# MethaneFlux_-_Copy.net
KiCad netlist of a schematic drawn in EAGLE
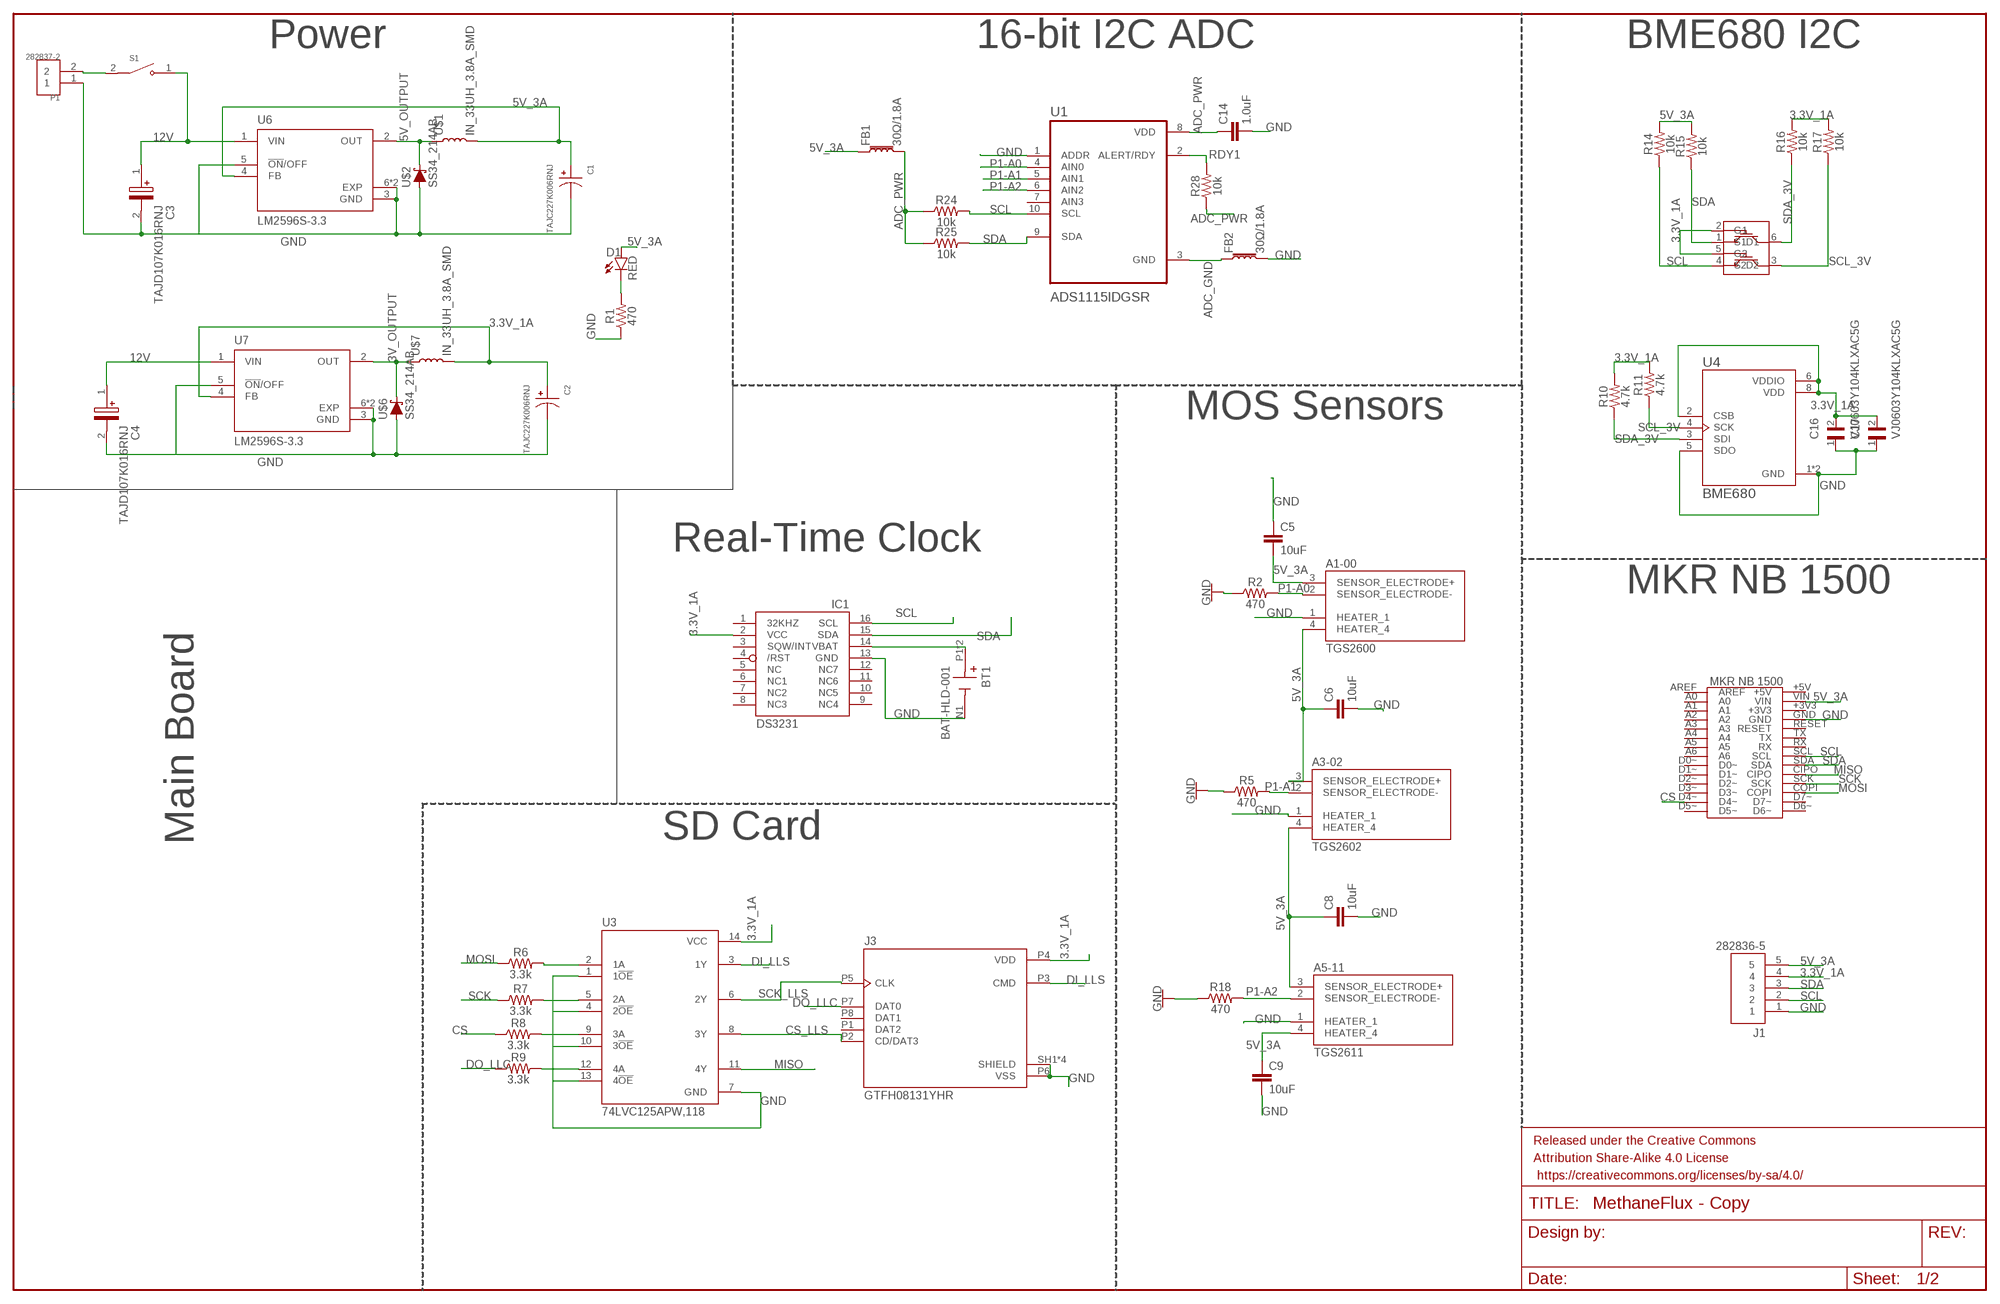
[diagram p0: schematic, sheet 1]
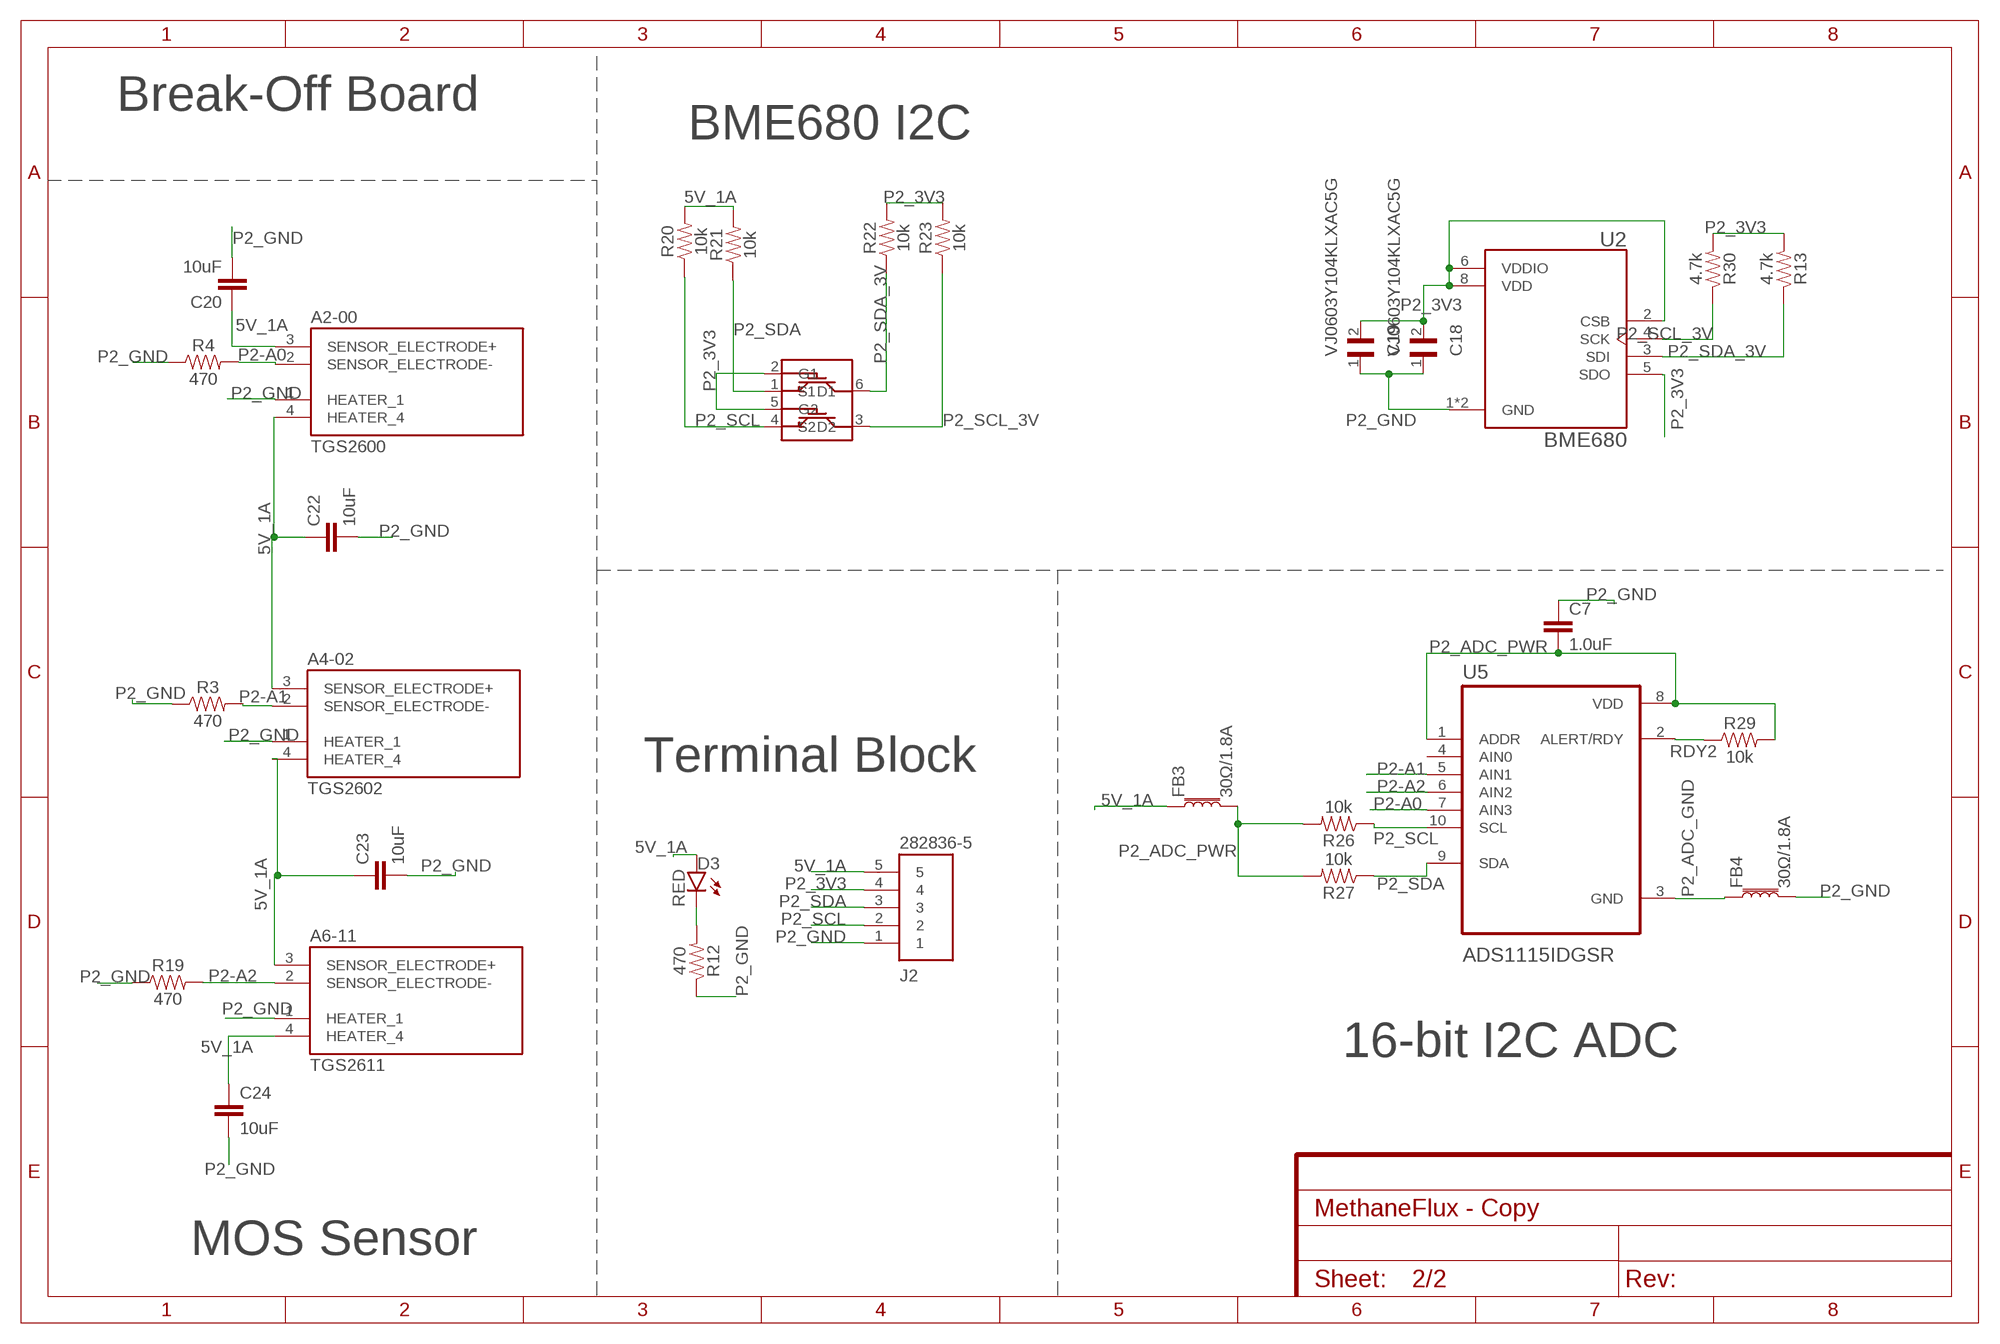
[diagram p1: schematic, sheet 2]

(export (version "E")
  (design (tool "Eeschema 10.0.6"))
  (components
    (comp (ref "A2-00")
      (value "TGS2600")
      (footprint "eagle-import:TO255P920H830-4")
      (fields (field (name "MF") "Figaro"))
      (libsource (lib "eagle-import") (part "TGS2600"))
    )
    (comp (ref "A4-02")
      (value "TGS2602")
      (footprint "eagle-import:TGS2602")
      (libsource (lib "eagle-import") (part "TGS2602"))
    )
    (comp (ref "A6-11")
      (value "TGS2611")
      (footprint "eagle-import:TGS2611")
      (libsource (lib "eagle-import") (part "TGS2611"))
    )
    (comp (ref "C7")
      (value "1.0uF")
      (footprint "eagle-import:0603")
      (libsource (lib "eagle-import") (part "1.0UF-0603-16V-10%"))
    )
    (comp (ref "C18")
      (value "VJ0603Y104KLXAC5G")
      (footprint "eagle-import:CAPC1608X92N")
      (fields (field (name "MF") "Vishay"))
      (libsource (lib "eagle-import") (part "VJ0603Y104KLXAC5G"))
    )
    (comp (ref "C19")
      (value "VJ0603Y104KLXAC5G")
      (footprint "eagle-import:CAPC1608X92N")
      (fields (field (name "MF") "Vishay"))
      (libsource (lib "eagle-import") (part "VJ0603Y104KLXAC5G"))
    )
    (comp (ref "C20")
      (value "10uF")
      (footprint "eagle-import:0603")
      (libsource (lib "eagle-import") (part "10UF-0603-6.3V-20%"))
    )
    (comp (ref "C22")
      (value "10uF")
      (footprint "eagle-import:0603")
      (libsource (lib "eagle-import") (part "10UF-0603-6.3V-20%"))
    )
    (comp (ref "C23")
      (value "10uF")
      (footprint "eagle-import:0603")
      (libsource (lib "eagle-import") (part "10UF-0603-6.3V-20%"))
    )
    (comp (ref "C24")
      (value "10uF")
      (footprint "eagle-import:0603")
      (libsource (lib "eagle-import") (part "10UF-0603-6.3V-20%"))
    )
    (comp (ref "D3")
      (value "RED")
      (footprint "eagle-import:LED-0603")
      (libsource (lib "eagle-import") (part "LED-RED0603"))
    )
    (comp (ref "FB3")
      (value "30Ω/1.8A")
      (footprint "eagle-import:0603")
      (libsource (lib "eagle-import") (part "FERRITE_BEAD-0603"))
    )
    (comp (ref "FB4")
      (value "30Ω/1.8A")
      (footprint "eagle-import:0603")
      (libsource (lib "eagle-import") (part "FERRITE_BEAD-0603"))
    )
    (comp (ref "J2")
      (value "282836-5")
      (footprint "eagle-import:TE_282836-5")
      (fields (field (name "MF") "TE Connectivity"))
      (libsource (lib "eagle-import") (part "282836-5"))
    )
    (comp (ref "R3")
      (value "470")
      (footprint "eagle-import:0603")
      (libsource (lib "eagle-import") (part "470OHM-0603-1/10W-1%"))
    )
    (comp (ref "R4")
      (value "470")
      (footprint "eagle-import:0603")
      (libsource (lib "eagle-import") (part "470OHM-0603-1/10W-1%"))
    )
    (comp (ref "R12")
      (value "470")
      (footprint "eagle-import:0603")
      (libsource (lib "eagle-import") (part "470OHM-0603-1/10W-1%"))
    )
    (comp (ref "R13")
      (value "4.7k")
      (footprint "eagle-import:0603")
      (libsource (lib "eagle-import") (part "4.7KOHM-0603-1/10W-1%"))
    )
    (comp (ref "R19")
      (value "470")
      (footprint "eagle-import:0603")
      (libsource (lib "eagle-import") (part "470OHM-0603-1/10W-1%"))
    )
    (comp (ref "R20")
      (value "10k")
      (footprint "eagle-import:0603")
      (libsource (lib "eagle-import") (part "10KOHM-0603-1/10W-1%"))
    )
    (comp (ref "R21")
      (value "10k")
      (footprint "eagle-import:0603")
      (libsource (lib "eagle-import") (part "10KOHM-0603-1/10W-1%"))
    )
    (comp (ref "R22")
      (value "10k")
      (footprint "eagle-import:0603")
      (libsource (lib "eagle-import") (part "10KOHM-0603-1/10W-1%"))
    )
    (comp (ref "R23")
      (value "10k")
      (footprint "eagle-import:0603")
      (libsource (lib "eagle-import") (part "10KOHM-0603-1/10W-1%"))
    )
    (comp (ref "R26")
      (value "10k")
      (footprint "eagle-import:0603")
      (libsource (lib "eagle-import") (part "10KOHM-0603-1/10W-1%"))
    )
    (comp (ref "R27")
      (value "10k")
      (footprint "eagle-import:0603")
      (libsource (lib "eagle-import") (part "10KOHM-0603-1/10W-1%"))
    )
    (comp (ref "R29")
      (value "10k")
      (footprint "eagle-import:0603")
      (libsource (lib "eagle-import") (part "10KOHM-0603-1/10W-1%"))
    )
    (comp (ref "R30")
      (value "4.7k")
      (footprint "eagle-import:0603")
      (libsource (lib "eagle-import") (part "4.7KOHM-0603-1/10W-1%"))
    )
    (comp (ref "U$4")
      (value "2N7002DW")
      (footprint "eagle-import:SOT363")
      (fields (field (name "MF") "onsemi"))
      (libsource (lib "eagle-import") (part "2N7002DW"))
    )
    (comp (ref "U2")
      (value "BME680")
      (footprint "eagle-import:PSON80P300X300X100-8N")
      (fields (field (name "MF") "Bosch Sensortec"))
      (libsource (lib "eagle-import") (part "BME680"))
    )
    (comp (ref "U5")
      (value "ADS1115IDGSR")
      (footprint "eagle-import:SOP50P490X110-10N")
      (fields (field (name "MF") "Texas Instruments"))
      (libsource (lib "eagle-import") (part "ADS1115IDGSR"))
    )
    (comp (ref "A1-00")
      (value "TGS2600")
      (footprint "eagle-import:TO255P920H830-4")
      (fields (field (name "MF") "Figaro"))
      (libsource (lib "eagle-import") (part "TGS2600"))
    )
    (comp (ref "A3-02")
      (value "TGS2602")
      (footprint "eagle-import:TGS2602")
      (libsource (lib "eagle-import") (part "TGS2602"))
    )
    (comp (ref "A5-11")
      (value "TGS2611")
      (footprint "eagle-import:TGS2611")
      (libsource (lib "eagle-import") (part "TGS2611"))
    )
    (comp (ref "BT1")
      (value "BAT-HLD-001")
      (footprint "eagle-import:BAT_BAT-HLD-001")
      (fields (field (name "MF") "Linx Technologies"))
      (libsource (lib "eagle-import") (part "BAT-HLD-001"))
    )
    (comp (ref "C1")
      (value "TAJC227K006RNJ")
      (footprint "eagle-import:CAPPM6032X280N")
      (fields (field (name "DIGIKEY_PART_NUMBER") "478-1713-2-ND") (field (name "MF") "KYOCERA AVX"))
      (libsource (lib "eagle-import") (part "TAJC227K006RNJ"))
    )
    (comp (ref "C2")
      (value "TAJC227K006RNJ")
      (footprint "eagle-import:CAPPM6032X280N")
      (fields (field (name "DIGIKEY_PART_NUMBER") "478-1713-2-ND") (field (name "MF") "KYOCERA AVX"))
      (libsource (lib "eagle-import") (part "TAJC227K006RNJ"))
    )
    (comp (ref "C3")
      (value "TAJD107K016RNJ")
      (footprint "eagle-import:CAPPM7344X310N")
      (fields (field (name "MF") "AVX"))
      (libsource (lib "eagle-import") (part "TAJD107K016RNJ"))
    )
    (comp (ref "C4")
      (value "TAJD107K016RNJ")
      (footprint "eagle-import:CAPPM7344X310N")
      (fields (field (name "MF") "AVX"))
      (libsource (lib "eagle-import") (part "TAJD107K016RNJ"))
    )
    (comp (ref "C5")
      (value "10uF")
      (footprint "eagle-import:0603")
      (libsource (lib "eagle-import") (part "10UF-0603-6.3V-20%"))
    )
    (comp (ref "C6")
      (value "10uF")
      (footprint "eagle-import:0603")
      (libsource (lib "eagle-import") (part "10UF-0603-6.3V-20%"))
    )
    (comp (ref "C8")
      (value "10uF")
      (footprint "eagle-import:0603")
      (libsource (lib "eagle-import") (part "10UF-0603-6.3V-20%"))
    )
    (comp (ref "C9")
      (value "10uF")
      (footprint "eagle-import:0603")
      (libsource (lib "eagle-import") (part "10UF-0603-6.3V-20%"))
    )
    (comp (ref "C14")
      (value "1.0uF")
      (footprint "eagle-import:0603")
      (libsource (lib "eagle-import") (part "1.0UF-0603-16V-10%"))
    )
    (comp (ref "C16")
      (value "VJ0603Y104KLXAC5G")
      (footprint "eagle-import:CAPC1608X92N")
      (fields (field (name "MF") "Vishay"))
      (libsource (lib "eagle-import") (part "VJ0603Y104KLXAC5G"))
    )
    (comp (ref "C17")
      (value "VJ0603Y104KLXAC5G")
      (footprint "eagle-import:CAPC1608X92N")
      (fields (field (name "MF") "Vishay"))
      (libsource (lib "eagle-import") (part "VJ0603Y104KLXAC5G"))
    )
    (comp (ref "D1")
      (value "RED")
      (footprint "eagle-import:LED-0603")
      (libsource (lib "eagle-import") (part "LED-RED0603"))
    )
    (comp (ref "FB1")
      (value "30Ω/1.8A")
      (footprint "eagle-import:0603")
      (libsource (lib "eagle-import") (part "FERRITE_BEAD-0603"))
    )
    (comp (ref "FB2")
      (value "30Ω/1.8A")
      (footprint "eagle-import:0603")
      (libsource (lib "eagle-import") (part "FERRITE_BEAD-0603"))
    )
    (comp (ref "FRAME1")
      (value "FRAME-LEDGER")
      (footprint "eagle-import:CREATIVE_COMMONS")
      (libsource (lib "eagle-import") (part "FRAME-LEDGER"))
    )
    (comp (ref "IC1")
      (value "DS3231/SO")
      (footprint "eagle-import:SO16W")
      (fields (field (name "MF") "Analog Devices") (field (name "MP") "DS3231"))
      (libsource (lib "eagle-import") (part "DS3231/SO"))
    )
    (comp (ref "J1")
      (value "282836-5")
      (footprint "eagle-import:TE_282836-5")
      (fields (field (name "MF") "TE Connectivity"))
      (libsource (lib "eagle-import") (part "282836-5"))
    )
    (comp (ref "J3")
      (value "GTFH08131YHR")
      (footprint "eagle-import:AMPHENOL_GTFH08131YHR")
      (fields (field (name "MF") "Amphenol ICC"))
      (libsource (lib "eagle-import") (part "GTFH08131YHR"))
    )
    (comp (ref "P1")
      (value "282837-2")
      (footprint "eagle-import:TE_282837-2")
      (fields (field (name "MF") "TE Connectivity"))
      (libsource (lib "eagle-import") (part "282837-2"))
    )
    (comp (ref "R1")
      (value "470")
      (footprint "eagle-import:0603")
      (libsource (lib "eagle-import") (part "470OHM-0603-1/10W-1%"))
    )
    (comp (ref "R2")
      (value "470")
      (footprint "eagle-import:0603")
      (libsource (lib "eagle-import") (part "470OHM-0603-1/10W-1%"))
    )
    (comp (ref "R5")
      (value "470")
      (footprint "eagle-import:0603")
      (libsource (lib "eagle-import") (part "470OHM-0603-1/10W-1%"))
    )
    (comp (ref "R6")
      (value "3.3k")
      (footprint "eagle-import:0603")
      (libsource (lib "eagle-import") (part "3.3KOHM-0603-1/10W-1%"))
    )
    (comp (ref "R7")
      (value "3.3k")
      (footprint "eagle-import:0603")
      (libsource (lib "eagle-import") (part "3.3KOHM-0603-1/10W-1%"))
    )
    (comp (ref "R8")
      (value "3.3k")
      (footprint "eagle-import:0603")
      (libsource (lib "eagle-import") (part "3.3KOHM-0603-1/10W-1%"))
    )
    (comp (ref "R9")
      (value "3.3k")
      (footprint "eagle-import:0603")
      (libsource (lib "eagle-import") (part "3.3KOHM-0603-1/10W-1%"))
    )
    (comp (ref "R10")
      (value "4.7k")
      (footprint "eagle-import:0603")
      (libsource (lib "eagle-import") (part "4.7KOHM-0603-1/10W-1%"))
    )
    (comp (ref "R11")
      (value "4.7k")
      (footprint "eagle-import:0603")
      (libsource (lib "eagle-import") (part "4.7KOHM-0603-1/10W-1%"))
    )
    (comp (ref "R14")
      (value "10k")
      (footprint "eagle-import:0603")
      (libsource (lib "eagle-import") (part "10KOHM-0603-1/10W-1%"))
    )
    (comp (ref "R15")
      (value "10k")
      (footprint "eagle-import:0603")
      (libsource (lib "eagle-import") (part "10KOHM-0603-1/10W-1%"))
    )
    (comp (ref "R16")
      (value "10k")
      (footprint "eagle-import:0603")
      (libsource (lib "eagle-import") (part "10KOHM-0603-1/10W-1%"))
    )
    (comp (ref "R17")
      (value "10k")
      (footprint "eagle-import:0603")
      (libsource (lib "eagle-import") (part "10KOHM-0603-1/10W-1%"))
    )
    (comp (ref "R18")
      (value "470")
      (footprint "eagle-import:0603")
      (libsource (lib "eagle-import") (part "470OHM-0603-1/10W-1%"))
    )
    (comp (ref "R24")
      (value "10k")
      (footprint "eagle-import:0603")
      (libsource (lib "eagle-import") (part "10KOHM-0603-1/10W-1%"))
    )
    (comp (ref "R25")
      (value "10k")
      (footprint "eagle-import:0603")
      (libsource (lib "eagle-import") (part "10KOHM-0603-1/10W-1%"))
    )
    (comp (ref "R28")
      (value "10k")
      (footprint "eagle-import:0603")
      (libsource (lib "eagle-import") (part "10KOHM-0603-1/10W-1%"))
    )
    (comp (ref "S1")
      (value "RB141C1100")
      (footprint "eagle-import:SW_RB141C1100")
      (fields (field (name "MF") "E-Switch"))
      (libsource (lib "eagle-import") (part "RB141C1100"))
    )
    (comp (ref "U$1")
      (value "IN_33UH_3.8A_SMD")
      (footprint "eagle-import:INDUCTOR_4X4MM")
      (libsource (lib "eagle-import") (part "IN_33UH_3.8A_SMD"))
    )
    (comp (ref "U$2")
      (value "SS34_214AB")
      (footprint "eagle-import:SOD-323")
      (libsource (lib "eagle-import") (part "SS34_214AB"))
    )
    (comp (ref "U$3")
      (value "2N7002DW")
      (footprint "eagle-import:SOT363")
      (fields (field (name "MF") "onsemi"))
      (libsource (lib "eagle-import") (part "2N7002DW"))
    )
    (comp (ref "U$5")
      (value "MKRNB1500")
      (footprint "eagle-import:MRKNB1500")
      (libsource (lib "eagle-import") (part "MKRNB1500"))
    )
    (comp (ref "U$6")
      (value "SS34_214AB")
      (footprint "eagle-import:SOD-323")
      (libsource (lib "eagle-import") (part "SS34_214AB"))
    )
    (comp (ref "U$7")
      (value "IN_33UH_3.8A_SMD")
      (footprint "eagle-import:INDUCTOR_4X4MM")
      (libsource (lib "eagle-import") (part "IN_33UH_3.8A_SMD"))
    )
    (comp (ref "U1")
      (value "ADS1115IDGSR")
      (footprint "eagle-import:SOP50P490X110-10N")
      (fields (field (name "MF") "Texas Instruments"))
      (libsource (lib "eagle-import") (part "ADS1115IDGSR"))
    )
    (comp (ref "U3")
      (value "74LVC125APW,118")
      (footprint "eagle-import:IC_74LVC125APW,118")
      (fields (field (name "MF") "Nexperia USA Inc."))
      (libsource (lib "eagle-import") (part "74LVC125APW,118"))
    )
    (comp (ref "U4")
      (value "BME680")
      (footprint "eagle-import:PSON80P300X300X100-8N")
      (fields (field (name "MF") "Bosch Sensortec"))
      (libsource (lib "eagle-import") (part "BME680"))
    )
    (comp (ref "U6")
      (value "LM2596S-3.3")
      (footprint "eagle-import:VREG_LM2596S-3.3")
      (fields (field (name "MF") "Texas Instruments"))
      (libsource (lib "eagle-import") (part "LM2596S-3.3"))
    )
    (comp (ref "U7")
      (value "LM2596S-3.3")
      (footprint "eagle-import:VREG_LM2596S-3.3")
      (fields (field (name "MF") "Texas Instruments"))
      (libsource (lib "eagle-import") (part "LM2596S-3.3"))
    )
  )
  (nets
    (net (code "1") (name "3.3V_1A") (class "Default")
      (node (ref "C16") (pin "2") (pinfunction "2_2") (pintype "passive"))
      (node (ref "C17") (pin "2") (pinfunction "2_2") (pintype "passive"))
      (node (ref "C2") (pin "1") (pinfunction "1_1") (pintype "passive"))
      (node (ref "IC1") (pin "2") (pinfunction "VCC_2") (pintype "power_in"))
      (node (ref "J1") (pin "4") (pinfunction "4_4") (pintype "passive"))
      (node (ref "J3") (pin "P4") (pinfunction "VDD_P4") (pintype "power_in"))
      (node (ref "R10") (pin "2") (pinfunction "2_2") (pintype "passive"))
      (node (ref "R11") (pin "2") (pinfunction "2_2") (pintype "passive"))
      (node (ref "R16") (pin "2") (pinfunction "2_2") (pintype "passive"))
      (node (ref "R17") (pin "2") (pinfunction "2_2") (pintype "passive"))
      (node (ref "U$3") (pin "2") (pinfunction "G1_2") (pintype "bidirectional"))
      (node (ref "U$3") (pin "5") (pinfunction "G2_5") (pintype "bidirectional"))
      (node (ref "U$7") (pin "P$2") (pinfunction "2_P$2") (pintype "passive"))
      (node (ref "U3") (pin "14") (pinfunction "VCC_14") (pintype "power_in"))
      (node (ref "U4") (pin "2") (pinfunction "CSB_2") (pintype "input"))
      (node (ref "U4") (pin "6") (pinfunction "VDDIO_6") (pintype "power_in"))
      (node (ref "U4") (pin "8") (pinfunction "VDD_8") (pintype "power_in"))
      (node (ref "U7") (pin "4") (pinfunction "FB_4") (pintype "input"))
    )
    (net (code "2") (name "3V_OUTPUT") (class "Default")
      (node (ref "U$6") (pin "ANODE") (pinfunction "C_ANODE") (pintype "passive"))
      (node (ref "U$7") (pin "P$1") (pinfunction "1_P$1") (pintype "passive"))
      (node (ref "U7") (pin "2") (pinfunction "OUT_2") (pintype "output"))
    )
    (net (code "3") (name "5V_1A") (class "Default")
      (node (ref "A2-00") (pin "3") (pinfunction "SENSOR_ELECTRODE+_3") (pintype "passive"))
      (node (ref "A2-00") (pin "4") (pinfunction "HEATER_4_4") (pintype "passive"))
      (node (ref "A4-02") (pin "3") (pinfunction "SENSOR_ELECTRODE+_3") (pintype "passive"))
      (node (ref "A4-02") (pin "4") (pinfunction "HEATER_4_4") (pintype "passive"))
      (node (ref "A6-11") (pin "3") (pinfunction "SENSOR_ELECTRODE+_3") (pintype "passive"))
      (node (ref "A6-11") (pin "4") (pinfunction "HEATER_4_4") (pintype "passive"))
      (node (ref "C20") (pin "1") (pinfunction "1_1") (pintype "passive"))
      (node (ref "C22") (pin "1") (pinfunction "1_1") (pintype "passive"))
      (node (ref "C23") (pin "1") (pinfunction "1_1") (pintype "passive"))
      (node (ref "C24") (pin "1") (pinfunction "1_1") (pintype "passive"))
      (node (ref "D3") (pin "A") (pinfunction "A_A") (pintype "passive"))
      (node (ref "FB3") (pin "1") (pinfunction "1_1") (pintype "passive"))
      (node (ref "J2") (pin "5") (pinfunction "5_5") (pintype "passive"))
      (node (ref "R20") (pin "2") (pinfunction "2_2") (pintype "passive"))
      (node (ref "R21") (pin "2") (pinfunction "2_2") (pintype "passive"))
    )
    (net (code "4") (name "5V_3A") (class "Default")
      (node (ref "A1-00") (pin "3") (pinfunction "SENSOR_ELECTRODE+_3") (pintype "passive"))
      (node (ref "A1-00") (pin "4") (pinfunction "HEATER_4_4") (pintype "passive"))
      (node (ref "A3-02") (pin "3") (pinfunction "SENSOR_ELECTRODE+_3") (pintype "passive"))
      (node (ref "A3-02") (pin "4") (pinfunction "HEATER_4_4") (pintype "passive"))
      (node (ref "A5-11") (pin "3") (pinfunction "SENSOR_ELECTRODE+_3") (pintype "passive"))
      (node (ref "A5-11") (pin "4") (pinfunction "HEATER_4_4") (pintype "passive"))
      (node (ref "C1") (pin "1") (pinfunction "1_1") (pintype "passive"))
      (node (ref "C5") (pin "2") (pinfunction "2_2") (pintype "passive"))
      (node (ref "C6") (pin "1") (pinfunction "1_1") (pintype "passive"))
      (node (ref "C8") (pin "1") (pinfunction "1_1") (pintype "passive"))
      (node (ref "C9") (pin "1") (pinfunction "1_1") (pintype "passive"))
      (node (ref "D1") (pin "A") (pinfunction "A_A") (pintype "passive"))
      (node (ref "FB1") (pin "1") (pinfunction "1_1") (pintype "passive"))
      (node (ref "J1") (pin "5") (pinfunction "5_5") (pintype "passive"))
      (node (ref "R14") (pin "2") (pinfunction "2_2") (pintype "passive"))
      (node (ref "R15") (pin "2") (pinfunction "2_2") (pintype "passive"))
      (node (ref "U$1") (pin "P$2") (pinfunction "2_P$2") (pintype "passive"))
      (node (ref "U$5") (pin "VIN") (pinfunction "VIN_VIN") (pintype "bidirectional"))
      (node (ref "U6") (pin "4") (pinfunction "FB_4") (pintype "input"))
    )
    (net (code "5") (name "5V_OUTPUT") (class "Default")
      (node (ref "U$1") (pin "P$1") (pinfunction "1_P$1") (pintype "passive"))
      (node (ref "U$2") (pin "ANODE") (pinfunction "C_ANODE") (pintype "passive"))
      (node (ref "U6") (pin "2") (pinfunction "OUT_2") (pintype "output"))
    )
    (net (code "6") (name "12V") (class "Default")
      (node (ref "C3") (pin "1") (pinfunction "+_1") (pintype "bidirectional"))
      (node (ref "C4") (pin "1") (pinfunction "+_1") (pintype "bidirectional"))
      (node (ref "S1") (pin "1") (pinfunction "1_1") (pintype "passive"))
      (node (ref "U6") (pin "1") (pinfunction "VIN_1") (pintype "input"))
      (node (ref "U7") (pin "1") (pinfunction "VIN_1") (pintype "input"))
    )
    (net (code "7") (name "ADC_GND") (class "Default")
      (node (ref "FB2") (pin "1") (pinfunction "1_1") (pintype "passive"))
      (node (ref "U1") (pin "3") (pinfunction "GND_3") (pintype "power_in"))
    )
    (net (code "8") (name "ADC_PWR") (class "Default")
      (node (ref "C14") (pin "1") (pinfunction "1_1") (pintype "passive"))
      (node (ref "FB1") (pin "2") (pinfunction "2_2") (pintype "passive"))
      (node (ref "R24") (pin "1") (pinfunction "1_1") (pintype "passive"))
      (node (ref "R25") (pin "1") (pinfunction "1_1") (pintype "passive"))
      (node (ref "R28") (pin "1") (pinfunction "1_1") (pintype "passive"))
      (node (ref "U1") (pin "8") (pinfunction "VDD_8") (pintype "power_in"))
    )
    (net (code "9") (name "CS") (class "Default")
      (node (ref "R8") (pin "1") (pinfunction "1_1") (pintype "passive"))
      (node (ref "U$5") (pin "D4~") (pinfunction "D4~{}_D4~") (pintype "bidirectional"))
    )
    (net (code "10") (name "CS_LLS") (class "Default")
      (node (ref "J3") (pin "P2") (pinfunction "CD/DAT3_P2") (pintype "bidirectional"))
      (node (ref "U3") (pin "8") (pinfunction "3Y_8") (pintype "output"))
    )
    (net (code "11") (name "DI_LLS") (class "Default")
      (node (ref "J3") (pin "P3") (pinfunction "CMD_P3") (pintype "bidirectional"))
      (node (ref "U3") (pin "3") (pinfunction "1Y_3") (pintype "output"))
    )
    (net (code "12") (name "DO_LLC") (class "Default")
      (node (ref "J3") (pin "P7") (pinfunction "DAT0_P7") (pintype "bidirectional"))
      (node (ref "R9") (pin "1") (pinfunction "1_1") (pintype "passive"))
    )
    (net (code "13") (name "GND") (class "Default")
      (node (ref "A1-00") (pin "1") (pinfunction "HEATER_1_1") (pintype "passive"))
      (node (ref "A3-02") (pin "1") (pinfunction "HEATER_1_1") (pintype "passive"))
      (node (ref "A5-11") (pin "1") (pinfunction "HEATER_1_1") (pintype "passive"))
      (node (ref "BT1") (pin "N1") (pinfunction "-_N1") (pintype "passive"))
      (node (ref "C1") (pin "2") (pinfunction "2_2") (pintype "passive"))
      (node (ref "C14") (pin "2") (pinfunction "2_2") (pintype "passive"))
      (node (ref "C16") (pin "1") (pinfunction "1_1") (pintype "passive"))
      (node (ref "C17") (pin "1") (pinfunction "1_1") (pintype "passive"))
      (node (ref "C2") (pin "2") (pinfunction "2_2") (pintype "passive"))
      (node (ref "C3") (pin "2") (pinfunction "-_2") (pintype "bidirectional"))
      (node (ref "C4") (pin "2") (pinfunction "-_2") (pintype "bidirectional"))
      (node (ref "C5") (pin "1") (pinfunction "1_1") (pintype "passive"))
      (node (ref "C6") (pin "2") (pinfunction "2_2") (pintype "passive"))
      (node (ref "C8") (pin "2") (pinfunction "2_2") (pintype "passive"))
      (node (ref "C9") (pin "2") (pinfunction "2_2") (pintype "passive"))
      (node (ref "FB2") (pin "2") (pinfunction "2_2") (pintype "passive"))
      (node (ref "IC1") (pin "13") (pinfunction "GND_13") (pintype "power_in"))
      (node (ref "J1") (pin "1") (pinfunction "1_1") (pintype "passive"))
      (node (ref "J3") (pin "P6") (pinfunction "VSS_P6") (pintype "power_in"))
      (node (ref "J3") (pin "SH1") (pinfunction "SHIELD_SH1") (pintype "power_in"))
      (node (ref "J3") (pin "SH2") (pinfunction "SHIELD_SH2") (pintype "power_in"))
      (node (ref "J3") (pin "SH3") (pinfunction "SHIELD_SH3") (pintype "power_in"))
      (node (ref "J3") (pin "SH4") (pinfunction "SHIELD_SH4") (pintype "power_in"))
      (node (ref "P1") (pin "1") (pinfunction "1_1") (pintype "passive"))
      (node (ref "R1") (pin "1") (pinfunction "1_1") (pintype "passive"))
      (node (ref "R18") (pin "1") (pinfunction "1_1") (pintype "passive"))
      (node (ref "R2") (pin "1") (pinfunction "1_1") (pintype "passive"))
      (node (ref "R5") (pin "1") (pinfunction "1_1") (pintype "passive"))
      (node (ref "U$2") (pin "CATHODE") (pinfunction "A_CATHODE") (pintype "passive"))
      (node (ref "U$5") (pin "GND") (pinfunction "GND_GND") (pintype "bidirectional"))
      (node (ref "U$6") (pin "CATHODE") (pinfunction "A_CATHODE") (pintype "passive"))
      (node (ref "U1") (pin "1") (pinfunction "ADDR_1") (pintype "input"))
      (node (ref "U3") (pin "1") (pinfunction "1~{OE}_1") (pintype "input"))
      (node (ref "U3") (pin "10") (pinfunction "3~{OE}_10") (pintype "input"))
      (node (ref "U3") (pin "13") (pinfunction "4~{OE}_13") (pintype "input"))
      (node (ref "U3") (pin "4") (pinfunction "2~{OE}_4") (pintype "input"))
      (node (ref "U3") (pin "7") (pinfunction "GND_7") (pintype "power_in"))
      (node (ref "U4") (pin "1") (pinfunction "GND_1") (pintype "power_in"))
      (node (ref "U4") (pin "5") (pinfunction "SDO_5") (pintype "bidirectional"))
      (node (ref "U4") (pin "7") (pinfunction "GND_7") (pintype "power_in"))
      (node (ref "U6") (pin "3") (pinfunction "GND_3") (pintype "power_in"))
      (node (ref "U6") (pin "5") (pinfunction "~{ON}/OFF_5") (pintype "input"))
      (node (ref "U6") (pin "6") (pinfunction "EXP_6") (pintype "power_in"))
      (node (ref "U6") (pin "7") (pinfunction "EXP_7") (pintype "power_in"))
      (node (ref "U7") (pin "3") (pinfunction "GND_3") (pintype "power_in"))
      (node (ref "U7") (pin "5") (pinfunction "~{ON}/OFF_5") (pintype "input"))
      (node (ref "U7") (pin "6") (pinfunction "EXP_6") (pintype "power_in"))
      (node (ref "U7") (pin "7") (pinfunction "EXP_7") (pintype "power_in"))
    )
    (net (code "14") (name "MISO") (class "Default")
      (node (ref "U$5") (pin "CIPO") (pinfunction "CIPO_CIPO") (pintype "bidirectional"))
      (node (ref "U3") (pin "11") (pinfunction "4Y_11") (pintype "output"))
    )
    (net (code "15") (name "MOSI") (class "Default")
      (node (ref "R6") (pin "1") (pinfunction "1_1") (pintype "passive"))
      (node (ref "U$5") (pin "COPI") (pinfunction "COPI_COPI") (pintype "bidirectional"))
    )
    (net (code "16") (name "Net-(D1-PadC)") (class "Default")
      (node (ref "D1") (pin "C") (pinfunction "C_C") (pintype "passive"))
      (node (ref "R1") (pin "2") (pinfunction "2_2") (pintype "passive"))
    )
    (net (code "17") (name "Net-(D3-PadC)") (class "Default")
      (node (ref "D3") (pin "C") (pinfunction "C_C") (pintype "passive"))
      (node (ref "R12") (pin "2") (pinfunction "2_2") (pintype "passive"))
    )
    (net (code "18") (name "Net-(IC1-VBAT)") (class "Default")
      (node (ref "BT1") (pin "P1") (pinfunction "+_P1") (pintype "passive"))
      (node (ref "BT1") (pin "P2") (pinfunction "+_P2") (pintype "passive"))
      (node (ref "IC1") (pin "14") (pinfunction "VBAT_14") (pintype "power_in"))
    )
    (net (code "19") (name "Net-(P1-Pad2)") (class "Default")
      (node (ref "P1") (pin "2") (pinfunction "2_2") (pintype "passive"))
      (node (ref "S1") (pin "2") (pinfunction "2_2") (pintype "passive"))
    )
    (net (code "20") (name "Net-(U3-1A)") (class "Default")
      (node (ref "R6") (pin "2") (pinfunction "2_2") (pintype "passive"))
      (node (ref "U3") (pin "2") (pinfunction "1A_2") (pintype "input"))
    )
    (net (code "21") (name "Net-(U3-2A)") (class "Default")
      (node (ref "R7") (pin "2") (pinfunction "2_2") (pintype "passive"))
      (node (ref "U3") (pin "5") (pinfunction "2A_5") (pintype "input"))
    )
    (net (code "22") (name "Net-(U3-3A)") (class "Default")
      (node (ref "R8") (pin "2") (pinfunction "2_2") (pintype "passive"))
      (node (ref "U3") (pin "9") (pinfunction "3A_9") (pintype "input"))
    )
    (net (code "23") (name "Net-(U3-4A)") (class "Default")
      (node (ref "R9") (pin "2") (pinfunction "2_2") (pintype "passive"))
      (node (ref "U3") (pin "12") (pinfunction "4A_12") (pintype "input"))
    )
    (net (code "24") (name "P1-A0") (class "Default")
      (node (ref "A1-00") (pin "2") (pinfunction "SENSOR_ELECTRODE-_2") (pintype "passive"))
      (node (ref "R2") (pin "2") (pinfunction "2_2") (pintype "passive"))
      (node (ref "U1") (pin "4") (pinfunction "AIN0_4") (pintype "input"))
    )
    (net (code "25") (name "P1-A1") (class "Default")
      (node (ref "A3-02") (pin "2") (pinfunction "SENSOR_ELECTRODE-_2") (pintype "passive"))
      (node (ref "R5") (pin "2") (pinfunction "2_2") (pintype "passive"))
      (node (ref "U1") (pin "5") (pinfunction "AIN1_5") (pintype "input"))
    )
    (net (code "26") (name "P1-A2") (class "Default")
      (node (ref "A5-11") (pin "2") (pinfunction "SENSOR_ELECTRODE-_2") (pintype "passive"))
      (node (ref "R18") (pin "2") (pinfunction "2_2") (pintype "passive"))
      (node (ref "U1") (pin "6") (pinfunction "AIN2_6") (pintype "input"))
    )
    (net (code "27") (name "P2-A0") (class "Default")
      (node (ref "A2-00") (pin "2") (pinfunction "SENSOR_ELECTRODE-_2") (pintype "passive"))
      (node (ref "R4") (pin "2") (pinfunction "2_2") (pintype "passive"))
      (node (ref "U5") (pin "7") (pinfunction "AIN3_7") (pintype "input"))
    )
    (net (code "28") (name "P2-A1") (class "Default")
      (node (ref "A4-02") (pin "2") (pinfunction "SENSOR_ELECTRODE-_2") (pintype "passive"))
      (node (ref "R3") (pin "2") (pinfunction "2_2") (pintype "passive"))
      (node (ref "U5") (pin "5") (pinfunction "AIN1_5") (pintype "input"))
    )
    (net (code "29") (name "P2-A2") (class "Default")
      (node (ref "A6-11") (pin "2") (pinfunction "SENSOR_ELECTRODE-_2") (pintype "passive"))
      (node (ref "R19") (pin "2") (pinfunction "2_2") (pintype "passive"))
      (node (ref "U5") (pin "6") (pinfunction "AIN2_6") (pintype "input"))
    )
    (net (code "30") (name "P2_3V3") (class "Default")
      (node (ref "C18") (pin "2") (pinfunction "2_2") (pintype "passive"))
      (node (ref "C19") (pin "2") (pinfunction "2_2") (pintype "passive"))
      (node (ref "J2") (pin "4") (pinfunction "4_4") (pintype "passive"))
      (node (ref "R13") (pin "2") (pinfunction "2_2") (pintype "passive"))
      (node (ref "R22") (pin "2") (pinfunction "2_2") (pintype "passive"))
      (node (ref "R23") (pin "2") (pinfunction "2_2") (pintype "passive"))
      (node (ref "R30") (pin "2") (pinfunction "2_2") (pintype "passive"))
      (node (ref "U$4") (pin "2") (pinfunction "G1_2") (pintype "bidirectional"))
      (node (ref "U$4") (pin "5") (pinfunction "G2_5") (pintype "bidirectional"))
      (node (ref "U2") (pin "2") (pinfunction "CSB_2") (pintype "input"))
      (node (ref "U2") (pin "5") (pinfunction "SDO_5") (pintype "bidirectional"))
      (node (ref "U2") (pin "6") (pinfunction "VDDIO_6") (pintype "power_in"))
      (node (ref "U2") (pin "8") (pinfunction "VDD_8") (pintype "power_in"))
    )
    (net (code "31") (name "P2_ADC_GND") (class "Default")
      (node (ref "FB4") (pin "1") (pinfunction "1_1") (pintype "passive"))
      (node (ref "U5") (pin "3") (pinfunction "GND_3") (pintype "power_in"))
    )
    (net (code "32") (name "P2_ADC_PWR") (class "Default")
      (node (ref "C7") (pin "2") (pinfunction "2_2") (pintype "passive"))
      (node (ref "FB3") (pin "2") (pinfunction "2_2") (pintype "passive"))
      (node (ref "R26") (pin "2") (pinfunction "2_2") (pintype "passive"))
      (node (ref "R27") (pin "2") (pinfunction "2_2") (pintype "passive"))
      (node (ref "R29") (pin "2") (pinfunction "2_2") (pintype "passive"))
      (node (ref "U5") (pin "1") (pinfunction "ADDR_1") (pintype "input"))
      (node (ref "U5") (pin "8") (pinfunction "VDD_8") (pintype "power_in"))
    )
    (net (code "33") (name "P2_GND") (class "Default")
      (node (ref "A2-00") (pin "1") (pinfunction "HEATER_1_1") (pintype "passive"))
      (node (ref "A4-02") (pin "1") (pinfunction "HEATER_1_1") (pintype "passive"))
      (node (ref "A6-11") (pin "1") (pinfunction "HEATER_1_1") (pintype "passive"))
      (node (ref "C18") (pin "1") (pinfunction "1_1") (pintype "passive"))
      (node (ref "C19") (pin "1") (pinfunction "1_1") (pintype "passive"))
      (node (ref "C20") (pin "2") (pinfunction "2_2") (pintype "passive"))
      (node (ref "C22") (pin "2") (pinfunction "2_2") (pintype "passive"))
      (node (ref "C23") (pin "2") (pinfunction "2_2") (pintype "passive"))
      (node (ref "C24") (pin "2") (pinfunction "2_2") (pintype "passive"))
      (node (ref "C7") (pin "1") (pinfunction "1_1") (pintype "passive"))
      (node (ref "FB4") (pin "2") (pinfunction "2_2") (pintype "passive"))
      (node (ref "J2") (pin "1") (pinfunction "1_1") (pintype "passive"))
      (node (ref "R12") (pin "1") (pinfunction "1_1") (pintype "passive"))
      (node (ref "R19") (pin "1") (pinfunction "1_1") (pintype "passive"))
      (node (ref "R3") (pin "1") (pinfunction "1_1") (pintype "passive"))
      (node (ref "R4") (pin "1") (pinfunction "1_1") (pintype "passive"))
      (node (ref "U2") (pin "1") (pinfunction "GND_1") (pintype "power_in"))
      (node (ref "U2") (pin "7") (pinfunction "GND_7") (pintype "power_in"))
    )
    (net (code "34") (name "P2_SCL") (class "Default")
      (node (ref "J2") (pin "2") (pinfunction "2_2") (pintype "passive"))
      (node (ref "R20") (pin "1") (pinfunction "1_1") (pintype "passive"))
      (node (ref "R26") (pin "1") (pinfunction "1_1") (pintype "passive"))
      (node (ref "U$4") (pin "4") (pinfunction "S2_4") (pintype "bidirectional"))
      (node (ref "U5") (pin "10") (pinfunction "SCL_10") (pintype "input"))
    )
    (net (code "35") (name "P2_SCL_3V") (class "Default")
      (node (ref "R23") (pin "1") (pinfunction "1_1") (pintype "passive"))
      (node (ref "R30") (pin "1") (pinfunction "1_1") (pintype "passive"))
      (node (ref "U$4") (pin "3") (pinfunction "D2_3") (pintype "bidirectional"))
      (node (ref "U2") (pin "4") (pinfunction "SCK_4") (pintype "input"))
    )
    (net (code "36") (name "P2_SDA") (class "Default")
      (node (ref "J2") (pin "3") (pinfunction "3_3") (pintype "passive"))
      (node (ref "R21") (pin "1") (pinfunction "1_1") (pintype "passive"))
      (node (ref "R27") (pin "1") (pinfunction "1_1") (pintype "passive"))
      (node (ref "U$4") (pin "1") (pinfunction "S1_1") (pintype "bidirectional"))
      (node (ref "U5") (pin "9") (pinfunction "SDA_9") (pintype "bidirectional"))
    )
    (net (code "37") (name "P2_SDA_3V") (class "Default")
      (node (ref "R13") (pin "1") (pinfunction "1_1") (pintype "passive"))
      (node (ref "R22") (pin "1") (pinfunction "1_1") (pintype "passive"))
      (node (ref "U$4") (pin "6") (pinfunction "D1_6") (pintype "bidirectional"))
      (node (ref "U2") (pin "3") (pinfunction "SDI_3") (pintype "bidirectional"))
    )
    (net (code "38") (name "RDY1") (class "Default")
      (node (ref "R28") (pin "2") (pinfunction "2_2") (pintype "passive"))
      (node (ref "U1") (pin "2") (pinfunction "ALERT/RDY_2") (pintype "output"))
    )
    (net (code "39") (name "RDY2") (class "Default")
      (node (ref "R29") (pin "1") (pinfunction "1_1") (pintype "passive"))
      (node (ref "U5") (pin "2") (pinfunction "ALERT/RDY_2") (pintype "output"))
    )
    (net (code "40") (name "SCK") (class "Default")
      (node (ref "R7") (pin "1") (pinfunction "1_1") (pintype "passive"))
      (node (ref "U$5") (pin "SCK") (pinfunction "SCK_SCK") (pintype "bidirectional"))
    )
    (net (code "41") (name "SCK_LLS") (class "Default")
      (node (ref "J3") (pin "P5") (pinfunction "CLK_P5") (pintype "bidirectional"))
      (node (ref "U3") (pin "6") (pinfunction "2Y_6") (pintype "output"))
    )
    (net (code "42") (name "SCL") (class "Default")
      (node (ref "IC1") (pin "16") (pinfunction "SCL_16") (pintype "bidirectional"))
      (node (ref "J1") (pin "2") (pinfunction "2_2") (pintype "passive"))
      (node (ref "R14") (pin "1") (pinfunction "1_1") (pintype "passive"))
      (node (ref "R24") (pin "2") (pinfunction "2_2") (pintype "passive"))
      (node (ref "U$3") (pin "4") (pinfunction "S2_4") (pintype "bidirectional"))
      (node (ref "U$5") (pin "SCL") (pinfunction "SCL_SCL") (pintype "bidirectional"))
      (node (ref "U1") (pin "10") (pinfunction "SCL_10") (pintype "input"))
    )
    (net (code "43") (name "SCL_3V") (class "Default")
      (node (ref "R11") (pin "1") (pinfunction "1_1") (pintype "passive"))
      (node (ref "R17") (pin "1") (pinfunction "1_1") (pintype "passive"))
      (node (ref "U$3") (pin "3") (pinfunction "D2_3") (pintype "bidirectional"))
      (node (ref "U4") (pin "4") (pinfunction "SCK_4") (pintype "input"))
    )
    (net (code "44") (name "SDA") (class "Default")
      (node (ref "IC1") (pin "15") (pinfunction "SDA_15") (pintype "bidirectional"))
      (node (ref "J1") (pin "3") (pinfunction "3_3") (pintype "passive"))
      (node (ref "R15") (pin "1") (pinfunction "1_1") (pintype "passive"))
      (node (ref "R25") (pin "2") (pinfunction "2_2") (pintype "passive"))
      (node (ref "U$3") (pin "1") (pinfunction "S1_1") (pintype "bidirectional"))
      (node (ref "U$5") (pin "SDA") (pinfunction "SDA_SDA") (pintype "bidirectional"))
      (node (ref "U1") (pin "9") (pinfunction "SDA_9") (pintype "bidirectional"))
    )
    (net (code "45") (name "SDA_3V") (class "Default")
      (node (ref "R10") (pin "1") (pinfunction "1_1") (pintype "passive"))
      (node (ref "R16") (pin "1") (pinfunction "1_1") (pintype "passive"))
      (node (ref "U$3") (pin "6") (pinfunction "D1_6") (pintype "bidirectional"))
      (node (ref "U4") (pin "3") (pinfunction "SDI_3") (pintype "bidirectional"))
    )
    (net (code "46") (name "unconnected-(IC1-32KHZ-Pad1)") (class "Default")
      (node (ref "IC1") (pin "1") (pinfunction "32KHZ_1") (pintype "output"))
    )
    (net (code "47") (name "unconnected-(IC1-NC-Pad5)") (class "Default")
      (node (ref "IC1") (pin "5") (pinfunction "NC_5") (pintype "no_connect"))
    )
    (net (code "48") (name "unconnected-(IC1-NC1-Pad6)") (class "Default")
      (node (ref "IC1") (pin "6") (pinfunction "NC1_6") (pintype "no_connect"))
    )
    (net (code "49") (name "unconnected-(IC1-NC2-Pad7)") (class "Default")
      (node (ref "IC1") (pin "7") (pinfunction "NC2_7") (pintype "no_connect"))
    )
    (net (code "50") (name "unconnected-(IC1-NC3-Pad8)") (class "Default")
      (node (ref "IC1") (pin "8") (pinfunction "NC3_8") (pintype "no_connect"))
    )
    (net (code "51") (name "unconnected-(IC1-NC4-Pad9)") (class "Default")
      (node (ref "IC1") (pin "9") (pinfunction "NC4_9") (pintype "no_connect"))
    )
    (net (code "52") (name "unconnected-(IC1-NC5-Pad10)") (class "Default")
      (node (ref "IC1") (pin "10") (pinfunction "NC5_10") (pintype "no_connect"))
    )
    (net (code "53") (name "unconnected-(IC1-NC6-Pad11)") (class "Default")
      (node (ref "IC1") (pin "11") (pinfunction "NC6_11") (pintype "no_connect"))
    )
    (net (code "54") (name "unconnected-(IC1-NC7-Pad12)") (class "Default")
      (node (ref "IC1") (pin "12") (pinfunction "NC7_12") (pintype "no_connect"))
    )
    (net (code "55") (name "unconnected-(IC1-SQW{slash}INT-Pad3)") (class "Default")
      (node (ref "IC1") (pin "3") (pinfunction "SQW/INT_3") (pintype "output"))
    )
    (net (code "56") (name "unconnected-(IC1-{slash}RST-Pad4)") (class "Default")
      (node (ref "IC1") (pin "4") (pinfunction "/RST_4") (pintype "passive"))
    )
    (net (code "57") (name "unconnected-(J3-DAT1-PadP8)") (class "Default")
      (node (ref "J3") (pin "P8") (pinfunction "DAT1_P8") (pintype "bidirectional"))
    )
    (net (code "58") (name "unconnected-(J3-DAT2-PadP1)") (class "Default")
      (node (ref "J3") (pin "P1") (pinfunction "DAT2_P1") (pintype "bidirectional"))
    )
    (net (code "59") (name "unconnected-(U$5-D0~{}-PadD0~)") (class "Default")
      (node (ref "U$5") (pin "D0~") (pinfunction "D0~{}_D0~") (pintype "bidirectional"))
    )
    (net (code "60") (name "unconnected-(U$5-D1~{}-PadD1~)") (class "Default")
      (node (ref "U$5") (pin "D1~") (pinfunction "D1~{}_D1~") (pintype "bidirectional"))
    )
    (net (code "61") (name "unconnected-(U$5-D2~{}-PadD2~)") (class "Default")
      (node (ref "U$5") (pin "D2~") (pinfunction "D2~{}_D2~") (pintype "bidirectional"))
    )
    (net (code "62") (name "unconnected-(U$5-D3~{}-PadD3~)") (class "Default")
      (node (ref "U$5") (pin "D3~") (pinfunction "D3~{}_D3~") (pintype "bidirectional"))
    )
    (net (code "63") (name "unconnected-(U$5-D5~{}-PadD5~)") (class "Default")
      (node (ref "U$5") (pin "D5~") (pinfunction "D5~{}_D5~") (pintype "bidirectional"))
    )
    (net (code "64") (name "unconnected-(U$5-D6~{}-PadD6~)") (class "Default")
      (node (ref "U$5") (pin "D6~") (pinfunction "D6~{}_D6~") (pintype "bidirectional"))
    )
    (net (code "65") (name "unconnected-(U$5-D7~{}-PadD7~)") (class "Default")
      (node (ref "U$5") (pin "D7~") (pinfunction "D7~{}_D7~") (pintype "bidirectional"))
    )
    (net (code "66") (name "unconnected-(U$5-Pad+3V3)") (class "Default")
      (node (ref "U$5") (pin "+3V3") (pinfunction "+3V3_+3V3") (pintype "bidirectional"))
    )
    (net (code "67") (name "unconnected-(U$5-Pad+5V)") (class "Default")
      (node (ref "U$5") (pin "+5V") (pinfunction "+5V_+5V") (pintype "bidirectional"))
    )
    (net (code "68") (name "unconnected-(U$5-PadA0)") (class "Default")
      (node (ref "U$5") (pin "A0") (pinfunction "A0_A0") (pintype "bidirectional"))
    )
    (net (code "69") (name "unconnected-(U$5-PadA1)") (class "Default")
      (node (ref "U$5") (pin "A1") (pinfunction "A1_A1") (pintype "bidirectional"))
    )
    (net (code "70") (name "unconnected-(U$5-PadA2)") (class "Default")
      (node (ref "U$5") (pin "A2") (pinfunction "A2_A2") (pintype "bidirectional"))
    )
    (net (code "71") (name "unconnected-(U$5-PadA3)") (class "Default")
      (node (ref "U$5") (pin "A3") (pinfunction "A3_A3") (pintype "bidirectional"))
    )
    (net (code "72") (name "unconnected-(U$5-PadA4)") (class "Default")
      (node (ref "U$5") (pin "A4") (pinfunction "A4_A4") (pintype "bidirectional"))
    )
    (net (code "73") (name "unconnected-(U$5-PadA5)") (class "Default")
      (node (ref "U$5") (pin "A5") (pinfunction "A5_A5") (pintype "bidirectional"))
    )
    (net (code "74") (name "unconnected-(U$5-PadA6)") (class "Default")
      (node (ref "U$5") (pin "A6") (pinfunction "A6_A6") (pintype "bidirectional"))
    )
    (net (code "75") (name "unconnected-(U$5-PadAREF)") (class "Default")
      (node (ref "U$5") (pin "AREF") (pinfunction "AREF_AREF") (pintype "bidirectional"))
    )
    (net (code "76") (name "unconnected-(U$5-PadRESET)") (class "Default")
      (node (ref "U$5") (pin "RESET") (pinfunction "RESET_RESET") (pintype "bidirectional"))
    )
    (net (code "77") (name "unconnected-(U$5-PadRX)") (class "Default")
      (node (ref "U$5") (pin "RX") (pinfunction "RX_RX") (pintype "bidirectional"))
    )
    (net (code "78") (name "unconnected-(U$5-PadTX)") (class "Default")
      (node (ref "U$5") (pin "TX") (pinfunction "TX_TX") (pintype "bidirectional"))
    )
    (net (code "79") (name "unconnected-(U1-AIN3-Pad7)") (class "Default")
      (node (ref "U1") (pin "7") (pinfunction "AIN3_7") (pintype "input"))
    )
    (net (code "80") (name "unconnected-(U5-AIN0-Pad4)") (class "Default")
      (node (ref "U5") (pin "4") (pinfunction "AIN0_4") (pintype "input"))
    )
  )
)
